# PiRFM12.net
KiCad netlist of a schematic drawn in EAGLE
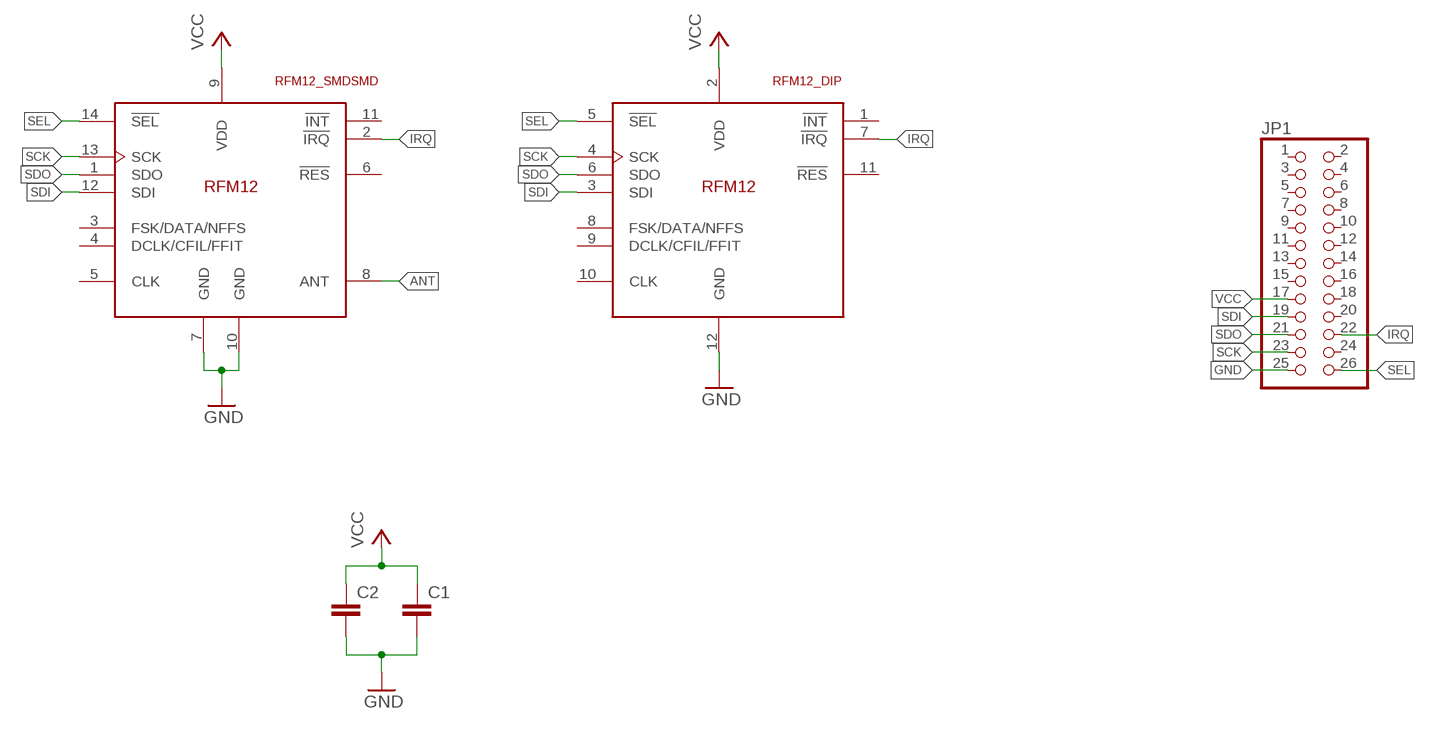
[diagram p0: schematic, sheet 1]

(export (version "E")
  (design (tool "Eeschema 10.0.6"))
  (components
    (comp (ref "C1")
      (value "C-EUC0805")
      (footprint "eagle-import:C0805")
      (libsource (lib "eagle-import") (part "C-EUC0805"))
    )
    (comp (ref "C2")
      (value "C-EUC0805")
      (footprint "eagle-import:C0805")
      (libsource (lib "eagle-import") (part "C-EUC0805"))
    )
    (comp (ref "JP1")
      (value "PINHD-2X13")
      (footprint "eagle-import:2X13")
      (libsource (lib "eagle-import") (part "PINHD-2X13"))
    )
    (comp (ref "U$1")
      (value "RFM12_SMDSMD")
      (footprint "eagle-import:RFM12")
      (libsource (lib "eagle-import") (part "RFM12_SMDSMD"))
    )
    (comp (ref "U$2")
      (value "RFM12_DIP")
      (footprint "eagle-import:DIL-2MM-2X06")
      (libsource (lib "eagle-import") (part "RFM12_DIP"))
    )
  )
  (nets
    (net (code "1") (name "ANT") (class "Default")
      (node (ref "U$1") (pin "8") (pinfunction "ANT_8") (pintype "bidirectional"))
    )
    (net (code "2") (name "GND") (class "Default")
      (node (ref "C1") (pin "2") (pinfunction "2_2") (pintype "passive"))
      (node (ref "C2") (pin "2") (pinfunction "2_2") (pintype "passive"))
      (node (ref "JP1") (pin "25") (pinfunction "25_25") (pintype "passive"))
      (node (ref "U$1") (pin "10") (pinfunction "GND_10") (pintype "passive"))
      (node (ref "U$1") (pin "7") (pinfunction "GND_7") (pintype "passive"))
      (node (ref "U$2") (pin "12") (pinfunction "GND_12") (pintype "passive"))
    )
    (net (code "3") (name "IRQ") (class "Default")
      (node (ref "JP1") (pin "22") (pinfunction "22_22") (pintype "passive"))
      (node (ref "U$1") (pin "2") (pinfunction "~{IRQ}_2") (pintype "output"))
      (node (ref "U$2") (pin "7") (pinfunction "~{IRQ}_7") (pintype "output"))
    )
    (net (code "4") (name "SCK") (class "Default")
      (node (ref "JP1") (pin "23") (pinfunction "23_23") (pintype "passive"))
      (node (ref "U$1") (pin "13") (pinfunction "SCK_13") (pintype "input"))
      (node (ref "U$2") (pin "4") (pinfunction "SCK_4") (pintype "input"))
    )
    (net (code "5") (name "SDI") (class "Default")
      (node (ref "JP1") (pin "19") (pinfunction "19_19") (pintype "passive"))
      (node (ref "U$1") (pin "12") (pinfunction "SDI_12") (pintype "input"))
      (node (ref "U$2") (pin "3") (pinfunction "SDI_3") (pintype "input"))
    )
    (net (code "6") (name "SDO") (class "Default")
      (node (ref "JP1") (pin "21") (pinfunction "21_21") (pintype "passive"))
      (node (ref "U$1") (pin "1") (pinfunction "SDO_1") (pintype "output"))
      (node (ref "U$2") (pin "6") (pinfunction "SDO_6") (pintype "output"))
    )
    (net (code "7") (name "SEL") (class "Default")
      (node (ref "JP1") (pin "26") (pinfunction "26_26") (pintype "passive"))
      (node (ref "U$1") (pin "14") (pinfunction "~{SEL}_14") (pintype "input"))
      (node (ref "U$2") (pin "5") (pinfunction "~{SEL}_5") (pintype "input"))
    )
    (net (code "8") (name "VCC") (class "Default")
      (node (ref "C1") (pin "1") (pinfunction "1_1") (pintype "passive"))
      (node (ref "C2") (pin "1") (pinfunction "1_1") (pintype "passive"))
      (node (ref "JP1") (pin "17") (pinfunction "17_17") (pintype "passive"))
      (node (ref "U$1") (pin "9") (pinfunction "VDD_9") (pintype "power_in"))
      (node (ref "U$2") (pin "2") (pinfunction "VDD_2") (pintype "power_in"))
    )
    (net (code "9") (name "unconnected-(JP1-Pad1)") (class "Default")
      (node (ref "JP1") (pin "1") (pinfunction "1_1") (pintype "passive"))
    )
    (net (code "10") (name "unconnected-(JP1-Pad2)") (class "Default")
      (node (ref "JP1") (pin "2") (pinfunction "2_2") (pintype "passive"))
    )
    (net (code "11") (name "unconnected-(JP1-Pad3)") (class "Default")
      (node (ref "JP1") (pin "3") (pinfunction "3_3") (pintype "passive"))
    )
    (net (code "12") (name "unconnected-(JP1-Pad4)") (class "Default")
      (node (ref "JP1") (pin "4") (pinfunction "4_4") (pintype "passive"))
    )
    (net (code "13") (name "unconnected-(JP1-Pad5)") (class "Default")
      (node (ref "JP1") (pin "5") (pinfunction "5_5") (pintype "passive"))
    )
    (net (code "14") (name "unconnected-(JP1-Pad6)") (class "Default")
      (node (ref "JP1") (pin "6") (pinfunction "6_6") (pintype "passive"))
    )
    (net (code "15") (name "unconnected-(JP1-Pad7)") (class "Default")
      (node (ref "JP1") (pin "7") (pinfunction "7_7") (pintype "passive"))
    )
    (net (code "16") (name "unconnected-(JP1-Pad8)") (class "Default")
      (node (ref "JP1") (pin "8") (pinfunction "8_8") (pintype "passive"))
    )
    (net (code "17") (name "unconnected-(JP1-Pad9)") (class "Default")
      (node (ref "JP1") (pin "9") (pinfunction "9_9") (pintype "passive"))
    )
    (net (code "18") (name "unconnected-(JP1-Pad10)") (class "Default")
      (node (ref "JP1") (pin "10") (pinfunction "10_10") (pintype "passive"))
    )
    (net (code "19") (name "unconnected-(JP1-Pad11)") (class "Default")
      (node (ref "JP1") (pin "11") (pinfunction "11_11") (pintype "passive"))
    )
    (net (code "20") (name "unconnected-(JP1-Pad12)") (class "Default")
      (node (ref "JP1") (pin "12") (pinfunction "12_12") (pintype "passive"))
    )
    (net (code "21") (name "unconnected-(JP1-Pad13)") (class "Default")
      (node (ref "JP1") (pin "13") (pinfunction "13_13") (pintype "passive"))
    )
    (net (code "22") (name "unconnected-(JP1-Pad14)") (class "Default")
      (node (ref "JP1") (pin "14") (pinfunction "14_14") (pintype "passive"))
    )
    (net (code "23") (name "unconnected-(JP1-Pad15)") (class "Default")
      (node (ref "JP1") (pin "15") (pinfunction "15_15") (pintype "passive"))
    )
    (net (code "24") (name "unconnected-(JP1-Pad16)") (class "Default")
      (node (ref "JP1") (pin "16") (pinfunction "16_16") (pintype "passive"))
    )
    (net (code "25") (name "unconnected-(JP1-Pad18)") (class "Default")
      (node (ref "JP1") (pin "18") (pinfunction "18_18") (pintype "passive"))
    )
    (net (code "26") (name "unconnected-(JP1-Pad20)") (class "Default")
      (node (ref "JP1") (pin "20") (pinfunction "20_20") (pintype "passive"))
    )
    (net (code "27") (name "unconnected-(JP1-Pad24)") (class "Default")
      (node (ref "JP1") (pin "24") (pinfunction "24_24") (pintype "passive"))
    )
    (net (code "28") (name "unconnected-(U$1-CLK-Pad5)") (class "Default")
      (node (ref "U$1") (pin "5") (pinfunction "CLK_5") (pintype "output"))
    )
    (net (code "29") (name "unconnected-(U$1-DCLK{slash}CFIL{slash}FFIT-Pad4)") (class "Default")
      (node (ref "U$1") (pin "4") (pinfunction "DCLK/CFIL/FFIT_4") (pintype "bidirectional"))
    )
    (net (code "30") (name "unconnected-(U$1-FSK{slash}DATA{slash}NFFS-Pad3)") (class "Default")
      (node (ref "U$1") (pin "3") (pinfunction "FSK/DATA/NFFS_3") (pintype "bidirectional"))
    )
    (net (code "31") (name "unconnected-(U$1-~{INT}-Pad11)") (class "Default")
      (node (ref "U$1") (pin "11") (pinfunction "~{INT}_11") (pintype "bidirectional"))
    )
    (net (code "32") (name "unconnected-(U$1-~{RES}-Pad6)") (class "Default")
      (node (ref "U$1") (pin "6") (pinfunction "~{RES}_6") (pintype "bidirectional"))
    )
    (net (code "33") (name "unconnected-(U$2-CLK-Pad10)") (class "Default")
      (node (ref "U$2") (pin "10") (pinfunction "CLK_10") (pintype "output"))
    )
    (net (code "34") (name "unconnected-(U$2-DCLK{slash}CFIL{slash}FFIT-Pad9)") (class "Default")
      (node (ref "U$2") (pin "9") (pinfunction "DCLK/CFIL/FFIT_9") (pintype "bidirectional"))
    )
    (net (code "35") (name "unconnected-(U$2-FSK{slash}DATA{slash}NFFS-Pad8)") (class "Default")
      (node (ref "U$2") (pin "8") (pinfunction "FSK/DATA/NFFS_8") (pintype "bidirectional"))
    )
    (net (code "36") (name "unconnected-(U$2-~{INT}-Pad1)") (class "Default")
      (node (ref "U$2") (pin "1") (pinfunction "~{INT}_1") (pintype "bidirectional"))
    )
    (net (code "37") (name "unconnected-(U$2-~{RES}-Pad11)") (class "Default")
      (node (ref "U$2") (pin "11") (pinfunction "~{RES}_11") (pintype "bidirectional"))
    )
  )
)
